# TB-01_V1_0.net
KiCad netlist of a schematic drawn in Altium Designer
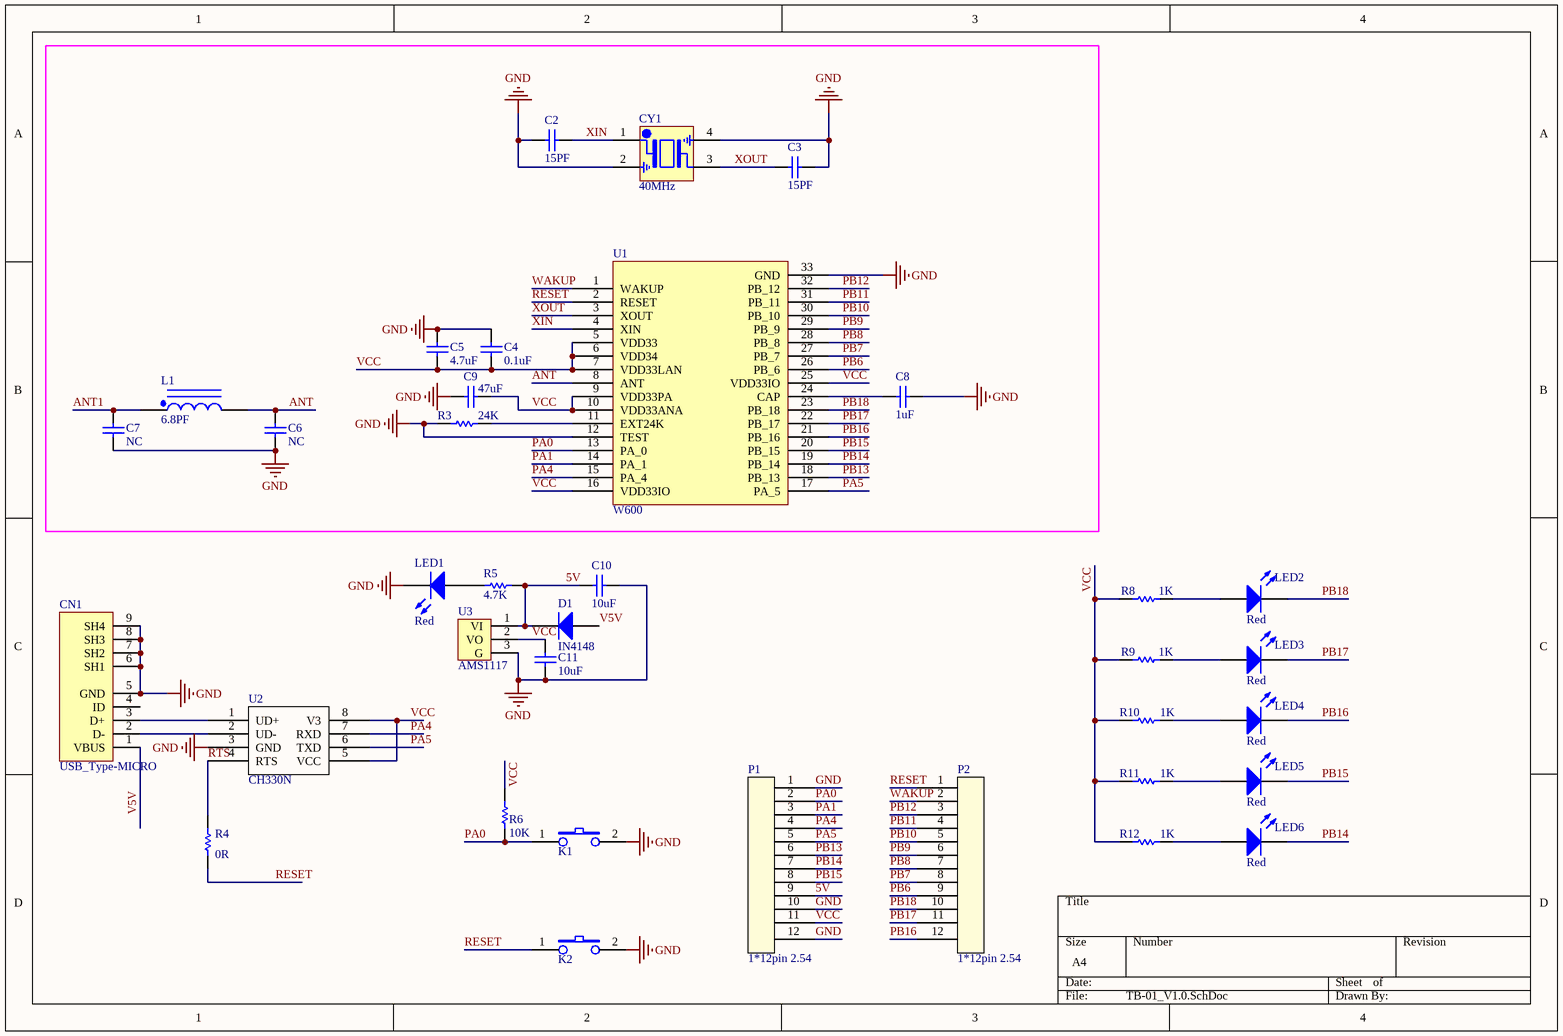
[diagram p0: TB-01_V1.0.SchDoc]

(export (version "E")
  (design (tool "Eeschema 10.0.6"))
  (components
    (comp (ref "C2") (value "15PF") (footprint "0402C") (libsource (lib "My_Lib") (part "CAP")))
    (comp (ref "C3") (value "15PF") (footprint "0402C") (libsource (lib "My_Lib") (part "CAP")))
    (comp (ref "C4") (value "0.1uF") (footprint "0402C") (libsource (lib "My_Lib") (part "CAP")))
    (comp (ref "C5") (value "4.7uF") (footprint "0603C") (libsource (lib "My_Lib") (part "CAP")))
    (comp (ref "C6") (value "NC") (footprint "0402C") (libsource (lib "My_Lib") (part "CAP")))
    (comp (ref "C7") (value "NC") (footprint "0402C") (libsource (lib "My_Lib") (part "CAP")))
    (comp (ref "C8") (value "1uF") (footprint "0402C") (libsource (lib "My_Lib") (part "CAP")))
    (comp (ref "C9") (value "47uF") (footprint "0805C") (libsource (lib "My_Lib") (part "CAP")))
    (comp (ref "C10") (value "10uF") (footprint "0603C") (libsource (lib "My_Lib") (part "CAP")))
    (comp (ref "C11") (value "10uF") (footprint "0603C") (libsource (lib "My_Lib") (part "CAP")))
    (comp (ref "CN1")
      (value "USB_Type-MICRO")
      (footprint "MICRO_USB_DIPB")
      (libsource (lib "My_Lib") (part "USB_Type-MICRO"))
    )
    (comp (ref "CY1") (value "40MHz") (footprint "CY3225") (libsource (lib "My_Lib") (part "CY3225")))
    (comp (ref "D1") (value "IN4148") (footprint "1n5819") (libsource (lib "My_Lib") (part "IN4148")))
    (comp (ref "K1") (value "Button") (footprint "BUTTON3*4*2") (libsource (lib "My_Lib") (part "Button")))
    (comp (ref "K2") (value "Button") (footprint "BUTTON3*4*2") (libsource (lib "My_Lib") (part "Button")))
    (comp (ref "L1") (value "6.8PF") (footprint "0402L") (libsource (lib "My_Lib") (part "L")))
    (comp (ref "LED1") (value "Red") (footprint "0603LED") (libsource (lib "My_Lib") (part "LED")))
    (comp (ref "LED2") (value "Red") (footprint "0603LED") (libsource (lib "My_Lib") (part "LED")))
    (comp (ref "LED3") (value "Red") (footprint "0603LED") (libsource (lib "My_Lib") (part "LED")))
    (comp (ref "LED4") (value "Red") (footprint "0603LED") (libsource (lib "My_Lib") (part "LED")))
    (comp (ref "LED5") (value "Red") (footprint "0603LED") (libsource (lib "My_Lib") (part "LED")))
    (comp (ref "LED6") (value "Red") (footprint "0603LED") (libsource (lib "My_Lib") (part "LED")))
    (comp (ref "P1")
      (value "1*12pin 2.54")
      (footprint "1*12PIN 2.54")
      (libsource (lib "") (part "1*12pin 2.54_1"))
    )
    (comp (ref "P2")
      (value "1*12pin 2.54")
      (footprint "1*12PIN 2.54")
      (libsource (lib "My_Lib") (part "1*12pin 2.54"))
    )
    (comp (ref "R3") (value "24K") (footprint "0402R") (libsource (lib "My_Lib") (part "RES")))
    (comp (ref "R4") (value "0R") (footprint "0402R") (libsource (lib "My_Lib") (part "RES")))
    (comp (ref "R5") (value "4.7K") (footprint "0402R") (libsource (lib "My_Lib") (part "RES")))
    (comp (ref "R6") (value "10K") (footprint "0402R") (libsource (lib "My_Lib") (part "RES")))
    (comp (ref "R8") (value "1K") (footprint "0402R") (libsource (lib "My_Lib") (part "RES")))
    (comp (ref "R9") (value "1K") (footprint "0402R") (libsource (lib "My_Lib") (part "RES")))
    (comp (ref "R10") (value "1K") (footprint "0402R") (libsource (lib "My_Lib") (part "RES")))
    (comp (ref "R11") (value "1K") (footprint "0402R") (libsource (lib "My_Lib") (part "RES")))
    (comp (ref "R12") (value "1K") (footprint "0402R") (libsource (lib "My_Lib") (part "RES")))
    (comp (ref "U1") (value "W600") (footprint "W600") (libsource (lib "My_Lib") (part "W600")))
    (comp (ref "U2") (value "CH330N") (footprint "CH330N") (libsource (lib "My_Lib") (part "CH330N")))
    (comp (ref "U3") (value "AMS1117") (footprint "AMS1117") (libsource (lib "Integrated") (part "AMS1117")))
  )
  (nets
    (net (code "1") (name "/5V") (class "Default")
      (node (ref "C10") (pin "2") (pinfunction "2_2") (pintype "passive"))
      (node (ref "D1") (pin "2") (pinfunction "K_2") (pintype "passive"))
      (node (ref "P1") (pin "9") (pinfunction "9_9") (pintype "passive"))
      (node (ref "R5") (pin "2") (pinfunction "2_2") (pintype "passive"))
      (node (ref "U3") (pin "1") (pinfunction "VI_1") (pintype "passive"))
    )
    (net (code "2") (name "/ANT") (class "Default")
      (node (ref "C6") (pin "2") (pinfunction "2_2") (pintype "passive"))
      (node (ref "L1") (pin "2") (pinfunction "2_2") (pintype "passive"))
      (node (ref "U1") (pin "8") (pinfunction "ANT_8") (pintype "passive"))
    )
    (net (code "3") (name "/ANT1") (class "Default")
      (node (ref "C7") (pin "2") (pinfunction "2_2") (pintype "passive"))
      (node (ref "L1") (pin "1") (pinfunction "1_1") (pintype "passive"))
    )
    (net (code "4") (name "/PA0") (class "Default")
      (node (ref "K1") (pin "1") (pinfunction "A0_1") (pintype "passive"))
      (node (ref "P1") (pin "2") (pinfunction "2_2") (pintype "passive"))
      (node (ref "R6") (pin "1") (pinfunction "1_1") (pintype "passive"))
      (node (ref "U1") (pin "13") (pinfunction "PA_0_13") (pintype "passive"))
    )
    (net (code "5") (name "/PA1") (class "Default")
      (node (ref "P1") (pin "3") (pinfunction "3_3") (pintype "passive"))
      (node (ref "U1") (pin "14") (pinfunction "PA_1_14") (pintype "passive"))
    )
    (net (code "6") (name "/PA4") (class "Default")
      (node (ref "P1") (pin "4") (pinfunction "4_4") (pintype "passive"))
      (node (ref "U1") (pin "15") (pinfunction "PA_4_15") (pintype "passive"))
      (node (ref "U2") (pin "7") (pinfunction "RXD_7") (pintype "passive"))
    )
    (net (code "7") (name "/PA5") (class "Default")
      (node (ref "P1") (pin "5") (pinfunction "5_5") (pintype "passive"))
      (node (ref "U1") (pin "17") (pinfunction "PA_5_17") (pintype "passive"))
      (node (ref "U2") (pin "6") (pinfunction "TXD_6") (pintype "passive"))
    )
    (net (code "8") (name "/PB6") (class "Default")
      (node (ref "P2") (pin "9") (pinfunction "9_9") (pintype "passive"))
      (node (ref "U1") (pin "26") (pinfunction "PB_6_26") (pintype "passive"))
    )
    (net (code "9") (name "/PB7") (class "Default")
      (node (ref "P2") (pin "8") (pinfunction "8_8") (pintype "passive"))
      (node (ref "U1") (pin "27") (pinfunction "PB_7_27") (pintype "passive"))
    )
    (net (code "10") (name "/PB8") (class "Default")
      (node (ref "P2") (pin "7") (pinfunction "7_7") (pintype "passive"))
      (node (ref "U1") (pin "28") (pinfunction "PB_8_28") (pintype "passive"))
    )
    (net (code "11") (name "/PB9") (class "Default")
      (node (ref "P2") (pin "6") (pinfunction "6_6") (pintype "passive"))
      (node (ref "U1") (pin "29") (pinfunction "PB_9_29") (pintype "passive"))
    )
    (net (code "12") (name "/PB10") (class "Default")
      (node (ref "P2") (pin "5") (pinfunction "5_5") (pintype "passive"))
      (node (ref "U1") (pin "30") (pinfunction "PB_10_30") (pintype "passive"))
    )
    (net (code "13") (name "/PB11") (class "Default")
      (node (ref "P2") (pin "4") (pinfunction "4_4") (pintype "passive"))
      (node (ref "U1") (pin "31") (pinfunction "PB_11_31") (pintype "passive"))
    )
    (net (code "14") (name "/PB12") (class "Default")
      (node (ref "P2") (pin "3") (pinfunction "3_3") (pintype "passive"))
      (node (ref "U1") (pin "32") (pinfunction "PB_12_32") (pintype "passive"))
    )
    (net (code "15") (name "/PB13") (class "Default")
      (node (ref "P1") (pin "6") (pinfunction "6_6") (pintype "passive"))
      (node (ref "U1") (pin "18") (pinfunction "PB_13_18") (pintype "passive"))
    )
    (net (code "16") (name "/PB14") (class "Default")
      (node (ref "LED6") (pin "2") (pinfunction "K_2") (pintype "passive"))
      (node (ref "P1") (pin "7") (pinfunction "7_7") (pintype "passive"))
      (node (ref "U1") (pin "19") (pinfunction "PB_14_19") (pintype "passive"))
    )
    (net (code "17") (name "/PB15") (class "Default")
      (node (ref "LED5") (pin "2") (pinfunction "K_2") (pintype "passive"))
      (node (ref "P1") (pin "8") (pinfunction "8_8") (pintype "passive"))
      (node (ref "U1") (pin "20") (pinfunction "PB_15_20") (pintype "passive"))
    )
    (net (code "18") (name "/PB16") (class "Default")
      (node (ref "LED4") (pin "2") (pinfunction "K_2") (pintype "passive"))
      (node (ref "P2") (pin "12") (pinfunction "12_12") (pintype "passive"))
      (node (ref "U1") (pin "21") (pinfunction "PB_16_21") (pintype "passive"))
    )
    (net (code "19") (name "/PB17") (class "Default")
      (node (ref "LED3") (pin "2") (pinfunction "K_2") (pintype "passive"))
      (node (ref "P2") (pin "11") (pinfunction "11_11") (pintype "passive"))
      (node (ref "U1") (pin "22") (pinfunction "PB_17_22") (pintype "passive"))
    )
    (net (code "20") (name "/PB18") (class "Default")
      (node (ref "LED2") (pin "2") (pinfunction "K_2") (pintype "passive"))
      (node (ref "P2") (pin "10") (pinfunction "10_10") (pintype "passive"))
      (node (ref "U1") (pin "23") (pinfunction "PB_18_23") (pintype "passive"))
    )
    (net (code "21") (name "/RESET") (class "Default")
      (node (ref "K2") (pin "1") (pinfunction "A0_1") (pintype "passive"))
      (node (ref "P2") (pin "1") (pintype "passive"))
      (node (ref "R4") (pin "1") (pinfunction "1_1") (pintype "passive"))
      (node (ref "U1") (pin "2") (pinfunction "RESET_2") (pintype "passive"))
    )
    (net (code "22") (name "/RTS") (class "Default")
      (node (ref "R4") (pin "2") (pinfunction "2_2") (pintype "passive"))
      (node (ref "U2") (pin "4") (pinfunction "RTS_4") (pintype "passive"))
    )
    (net (code "23") (name "/V5V") (class "Default")
      (node (ref "CN1") (pin "1") (pinfunction "VBUS_1") (pintype "passive"))
      (node (ref "D1") (pin "1") (pinfunction "A_1") (pintype "passive"))
    )
    (net (code "24") (name "/VCC") (class "Default")
      (node (ref "C11") (pin "1") (pinfunction "1_1") (pintype "passive"))
      (node (ref "C4") (pin "1") (pinfunction "1_1") (pintype "passive"))
      (node (ref "C5") (pin "1") (pinfunction "1_1") (pintype "passive"))
      (node (ref "C9") (pin "2") (pinfunction "2_2") (pintype "passive"))
      (node (ref "P1") (pin "11") (pinfunction "11_11") (pintype "passive"))
      (node (ref "R10") (pin "2") (pinfunction "2_2") (pintype "passive"))
      (node (ref "R11") (pin "2") (pinfunction "2_2") (pintype "passive"))
      (node (ref "R12") (pin "2") (pinfunction "2_2") (pintype "passive"))
      (node (ref "R6") (pin "2") (pinfunction "2_2") (pintype "passive"))
      (node (ref "R8") (pin "2") (pinfunction "2_2") (pintype "passive"))
      (node (ref "R9") (pin "2") (pinfunction "2_2") (pintype "passive"))
      (node (ref "U1") (pin "10") (pinfunction "VDD33ANA_10") (pintype "passive"))
      (node (ref "U1") (pin "16") (pinfunction "VDD33IO_16") (pintype "passive"))
      (node (ref "U1") (pin "25") (pinfunction "VDD33IO_25") (pintype "passive"))
      (node (ref "U1") (pin "5") (pinfunction "VDD33_5") (pintype "passive"))
      (node (ref "U1") (pin "6") (pinfunction "VDD34_6") (pintype "passive"))
      (node (ref "U1") (pin "7") (pinfunction "VDD33LAN_7") (pintype "passive"))
      (node (ref "U1") (pin "9") (pinfunction "VDD33PA_9") (pintype "passive"))
      (node (ref "U2") (pin "5") (pinfunction "VCC_5") (pintype "passive"))
      (node (ref "U2") (pin "8") (pinfunction "V3_8") (pintype "passive"))
      (node (ref "U3") (pin "2") (pinfunction "VO_2") (pintype "passive"))
    )
    (net (code "25") (name "/WAKUP") (class "Default")
      (node (ref "P2") (pin "2") (pinfunction "2_2") (pintype "passive"))
      (node (ref "U1") (pin "1") (pinfunction "WAKUP_1") (pintype "passive"))
    )
    (net (code "26") (name "/XIN") (class "Default")
      (node (ref "C2") (pin "2") (pinfunction "2_2") (pintype "passive"))
      (node (ref "CY1") (pin "1") (pinfunction "IN/OUT_1") (pintype "passive"))
      (node (ref "U1") (pin "4") (pinfunction "XIN_4") (pintype "passive"))
    )
    (net (code "27") (name "/XOUT") (class "Default")
      (node (ref "C3") (pin "1") (pinfunction "1_1") (pintype "passive"))
      (node (ref "CY1") (pin "3") (pinfunction "IN/OUT_3") (pintype "passive"))
      (node (ref "U1") (pin "3") (pinfunction "XOUT_3") (pintype "passive"))
    )
    (net (code "28") (name "GND") (class "Default")
      (node (ref "C10") (pin "1") (pinfunction "1_1") (pintype "passive"))
      (node (ref "C11") (pin "2") (pinfunction "2_2") (pintype "passive"))
      (node (ref "C2") (pin "1") (pinfunction "1_1") (pintype "passive"))
      (node (ref "C3") (pin "2") (pinfunction "2_2") (pintype "passive"))
      (node (ref "C4") (pin "2") (pinfunction "2_2") (pintype "passive"))
      (node (ref "C5") (pin "2") (pinfunction "2_2") (pintype "passive"))
      (node (ref "C6") (pin "1") (pinfunction "1_1") (pintype "passive"))
      (node (ref "C7") (pin "1") (pinfunction "1_1") (pintype "passive"))
      (node (ref "C8") (pin "2") (pinfunction "2_2") (pintype "passive"))
      (node (ref "C9") (pin "1") (pinfunction "1_1") (pintype "passive"))
      (node (ref "CN1") (pin "5") (pinfunction "GND_5") (pintype "passive"))
      (node (ref "CN1") (pin "6") (pinfunction "SH1_6") (pintype "passive"))
      (node (ref "CN1") (pin "7") (pinfunction "SH2_7") (pintype "passive"))
      (node (ref "CN1") (pin "8") (pinfunction "SH3_8") (pintype "passive"))
      (node (ref "CN1") (pin "9") (pinfunction "SH4_9") (pintype "passive"))
      (node (ref "CY1") (pin "2") (pinfunction "GND_2") (pintype "passive"))
      (node (ref "CY1") (pin "4") (pinfunction "GND_4") (pintype "passive"))
      (node (ref "K1") (pin "2") (pinfunction "B0_2") (pintype "passive"))
      (node (ref "K2") (pin "2") (pinfunction "B0_2") (pintype "passive"))
      (node (ref "LED1") (pin "2") (pinfunction "K_2") (pintype "passive"))
      (node (ref "P1") (pin "1") (pintype "passive"))
      (node (ref "P1") (pin "10") (pinfunction "10_10") (pintype "passive"))
      (node (ref "P1") (pin "12") (pinfunction "12_12") (pintype "passive"))
      (node (ref "R3") (pin "1") (pinfunction "1_1") (pintype "passive"))
      (node (ref "U1") (pin "12") (pinfunction "TEST_12") (pintype "passive"))
      (node (ref "U1") (pin "33") (pinfunction "GND_33") (pintype "passive"))
      (node (ref "U2") (pin "3") (pinfunction "GND_3") (pintype "passive"))
      (node (ref "U3") (pin "3") (pinfunction "G_3") (pintype "passive"))
    )
    (net (code "29") (name "Net-(CN1-D+)") (class "Default")
      (node (ref "CN1") (pin "3") (pinfunction "D+_3") (pintype "passive"))
      (node (ref "U2") (pin "1") (pinfunction "UD+_1") (pintype "passive"))
    )
    (net (code "30") (name "Net-(CN1-D-)") (class "Default")
      (node (ref "CN1") (pin "2") (pinfunction "D-_2") (pintype "passive"))
      (node (ref "U2") (pin "2") (pinfunction "UD-_2") (pintype "passive"))
    )
    (net (code "31") (name "Net-(LED1-A)") (class "Default")
      (node (ref "LED1") (pin "1") (pinfunction "A_1") (pintype "passive"))
      (node (ref "R5") (pin "1") (pinfunction "1_1") (pintype "passive"))
    )
    (net (code "32") (name "Net-(LED2-A)") (class "Default")
      (node (ref "LED2") (pin "1") (pinfunction "A_1") (pintype "passive"))
      (node (ref "R8") (pin "1") (pinfunction "1_1") (pintype "passive"))
    )
    (net (code "33") (name "Net-(LED3-A)") (class "Default")
      (node (ref "LED3") (pin "1") (pinfunction "A_1") (pintype "passive"))
      (node (ref "R9") (pin "1") (pinfunction "1_1") (pintype "passive"))
    )
    (net (code "34") (name "Net-(LED4-A)") (class "Default")
      (node (ref "LED4") (pin "1") (pinfunction "A_1") (pintype "passive"))
      (node (ref "R10") (pin "1") (pinfunction "1_1") (pintype "passive"))
    )
    (net (code "35") (name "Net-(LED5-A)") (class "Default")
      (node (ref "LED5") (pin "1") (pinfunction "A_1") (pintype "passive"))
      (node (ref "R11") (pin "1") (pinfunction "1_1") (pintype "passive"))
    )
    (net (code "36") (name "Net-(LED6-A)") (class "Default")
      (node (ref "LED6") (pin "1") (pinfunction "A_1") (pintype "passive"))
      (node (ref "R12") (pin "1") (pinfunction "1_1") (pintype "passive"))
    )
    (net (code "37") (name "Net-(U1-CAP)") (class "Default")
      (node (ref "C8") (pin "1") (pinfunction "1_1") (pintype "passive"))
      (node (ref "U1") (pin "24") (pinfunction "CAP_24") (pintype "passive"))
    )
    (net (code "38") (name "Net-(U1-EXT24K)") (class "Default")
      (node (ref "R3") (pin "2") (pinfunction "2_2") (pintype "passive"))
      (node (ref "U1") (pin "11") (pinfunction "EXT24K_11") (pintype "passive"))
    )
    (net (code "39") (name "unconnected-(CN1-ID-Pad4)") (class "Default")
      (node (ref "CN1") (pin "4") (pinfunction "ID_4") (pintype "passive"))
    )
  )
)
